# untitledV2.net
KiCad netlist of a schematic drawn in EAGLE
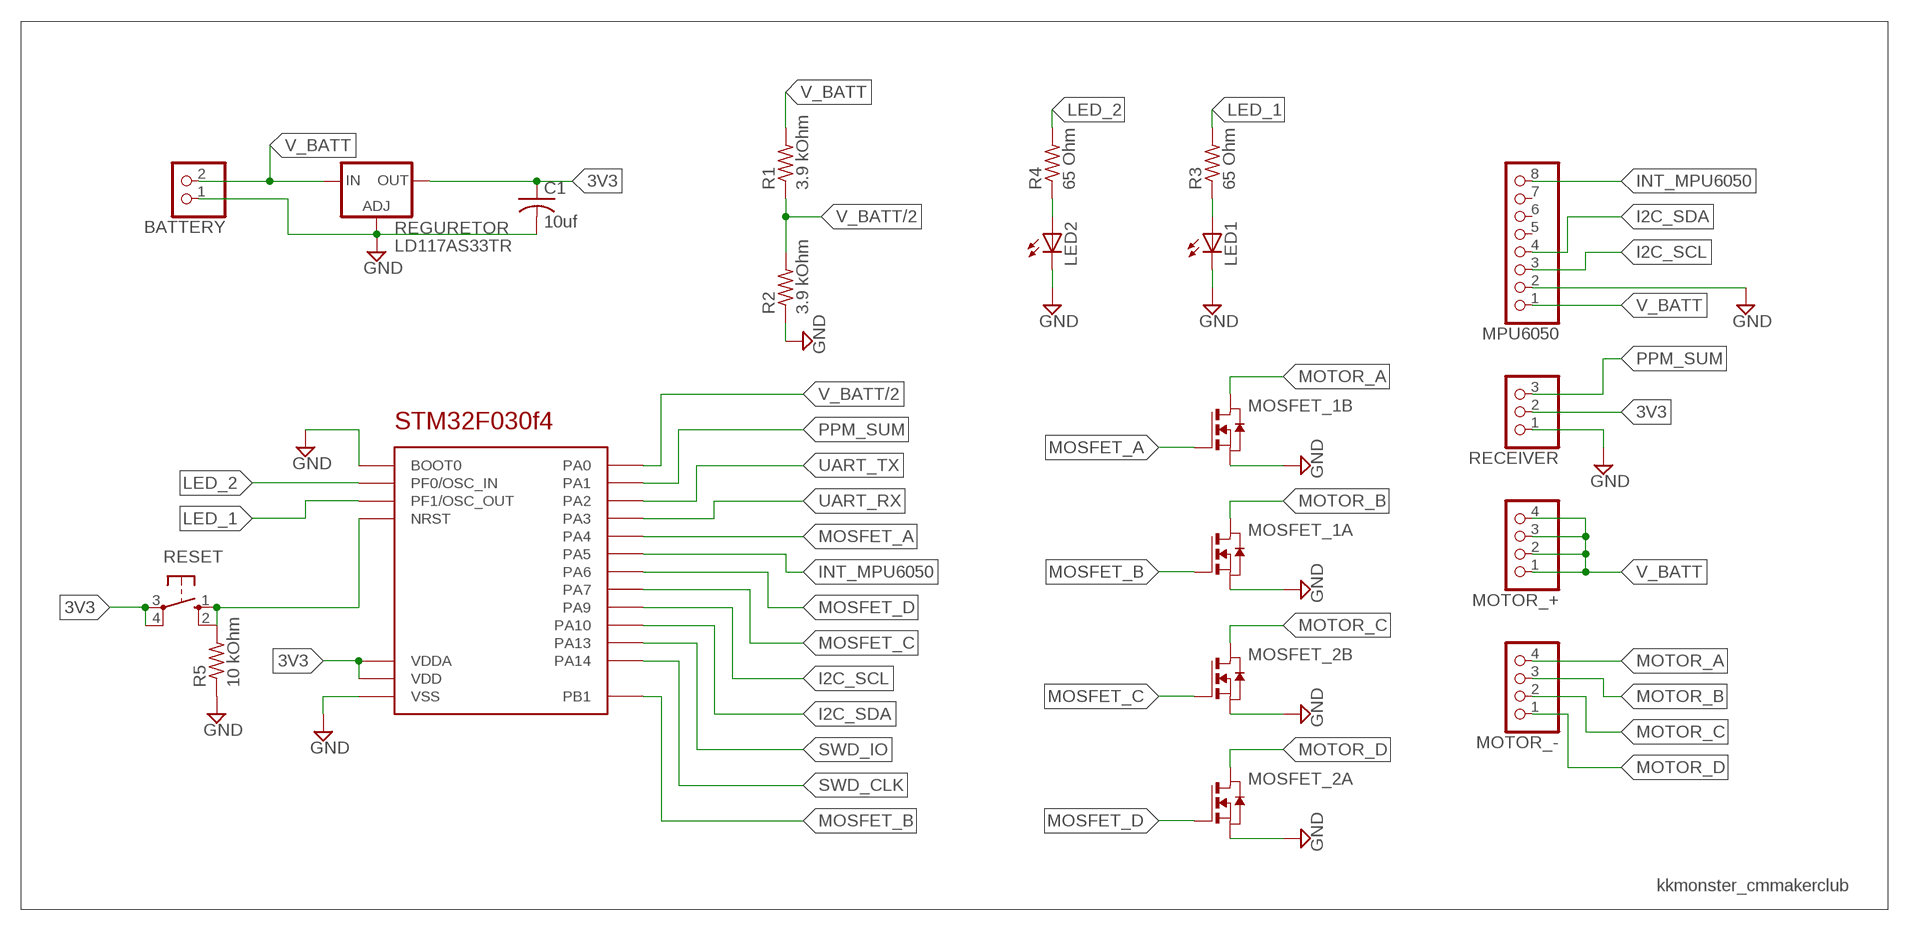
[diagram p0: schematic, sheet 1]

(export (version "E")
  (design (tool "Eeschema 10.0.6"))
  (components
    (comp (ref "BATTERY")
      (value "PINHD-1X2")
      (footprint "eagle-import:1X02")
      (libsource (lib "eagle-import") (part "PINHD-1X2"))
    )
    (comp (ref "C1")
      (value "10uf")
      (footprint "eagle-import:C1206")
      (libsource (lib "eagle-import") (part "C-USC1206"))
    )
    (comp (ref "LED1")
      (value "LEDSMT1206")
      (footprint "eagle-import:1206")
      (libsource (lib "eagle-import") (part "LEDSMT1206"))
    )
    (comp (ref "LED2")
      (value "LEDSMT1206")
      (footprint "eagle-import:1206")
      (libsource (lib "eagle-import") (part "LEDSMT1206"))
    )
    (comp (ref "MOSFET_1")
      (value "DMN3024LSD")
      (footprint "eagle-import:SO8")
      (libsource (lib "eagle-import") (part "DMN3024LSD"))
    )
    (comp (ref "MOSFET_2")
      (value "DMN3024LSD")
      (footprint "eagle-import:SO8")
      (libsource (lib "eagle-import") (part "DMN3024LSD"))
    )
    (comp (ref "MOTOR_+")
      (value "PINHD-1X4")
      (footprint "eagle-import:1X04")
      (libsource (lib "eagle-import") (part "PINHD-1X4"))
    )
    (comp (ref "MOTOR_-")
      (value "PINHD-1X4")
      (footprint "eagle-import:1X04")
      (libsource (lib "eagle-import") (part "PINHD-1X4"))
    )
    (comp (ref "MPU6050")
      (value "PINHD-1X8")
      (footprint "eagle-import:1X08")
      (libsource (lib "eagle-import") (part "PINHD-1X8"))
    )
    (comp (ref "R1")
      (value "3.9 kOhm")
      (footprint "eagle-import:R1206")
      (libsource (lib "eagle-import") (part "R-US_R1206"))
    )
    (comp (ref "R2")
      (value "3.9 kOhm")
      (footprint "eagle-import:R1206")
      (libsource (lib "eagle-import") (part "R-US_R1206"))
    )
    (comp (ref "R3")
      (value "65 Ohm")
      (footprint "eagle-import:R1206")
      (libsource (lib "eagle-import") (part "R-US_R1206"))
    )
    (comp (ref "R4")
      (value "65 Ohm")
      (footprint "eagle-import:R1206")
      (libsource (lib "eagle-import") (part "R-US_R1206"))
    )
    (comp (ref "R5")
      (value "10 kOhm")
      (footprint "eagle-import:R1206")
      (libsource (lib "eagle-import") (part "R-US_R1206"))
    )
    (comp (ref "RECEIVER")
      (value "PINHD-1X3")
      (footprint "eagle-import:1X03")
      (libsource (lib "eagle-import") (part "PINHD-1X3"))
    )
    (comp (ref "REGURETOR")
      (value "LD117AS33TR")
      (footprint "eagle-import:SOT223")
      (libsource (lib "eagle-import") (part "LD117A?S33TR"))
    )
    (comp (ref "RESET")
      (value "10-XX")
      (footprint "eagle-import:B3F-10XX")
      (fields (field (name "MPN") "B3F-1000"))
      (libsource (lib "eagle-import") (part "10-XX"))
    )
    (comp (ref "U$1")
      (value "STM32F030X4")
      (footprint "eagle-import:TSSOP20")
      (libsource (lib "eagle-import") (part "STM32F030X4"))
    )
  )
  (nets
    (net (code "1") (name "3V3") (class "Default")
      (node (ref "C1") (pin "1") (pinfunction "1_1") (pintype "passive"))
      (node (ref "RECEIVER") (pin "2") (pinfunction "2_2") (pintype "passive"))
      (node (ref "REGURETOR") (pin "4") (pinfunction "OUT_4") (pintype "passive"))
      (node (ref "RESET") (pin "3") (pinfunction "P_3") (pintype "passive"))
      (node (ref "RESET") (pin "4") (pinfunction "P1_4") (pintype "passive"))
      (node (ref "U$1") (pin "P$16") (pinfunction "VDD_P$16") (pintype "power_in"))
      (node (ref "U$1") (pin "P$5") (pinfunction "VDDA_P$5") (pintype "power_in"))
    )
    (net (code "2") (name "GND") (class "Default")
      (node (ref "BATTERY") (pin "1") (pinfunction "1_1") (pintype "passive"))
      (node (ref "C1") (pin "2") (pinfunction "2_2") (pintype "passive"))
      (node (ref "LED1") (pin "C") (pinfunction "C_C") (pintype "passive"))
      (node (ref "LED2") (pin "C") (pinfunction "C_C") (pintype "passive"))
      (node (ref "MOSFET_1") (pin "1") (pinfunction "S_1") (pintype "passive"))
      (node (ref "MOSFET_1") (pin "3") (pinfunction "S_3") (pintype "passive"))
      (node (ref "MOSFET_2") (pin "1") (pinfunction "S_1") (pintype "passive"))
      (node (ref "MOSFET_2") (pin "3") (pinfunction "S_3") (pintype "passive"))
      (node (ref "MPU6050") (pin "2") (pinfunction "2_2") (pintype "passive"))
      (node (ref "R2") (pin "1") (pinfunction "1_1") (pintype "passive"))
      (node (ref "R5") (pin "1") (pinfunction "1_1") (pintype "passive"))
      (node (ref "RECEIVER") (pin "1") (pinfunction "1_1") (pintype "passive"))
      (node (ref "REGURETOR") (pin "1") (pinfunction "ADJ_1") (pintype "input"))
      (node (ref "U$1") (pin "P$1") (pinfunction "BOOT0_P$1") (pintype "power_in"))
      (node (ref "U$1") (pin "P$15") (pinfunction "VSS_P$15") (pintype "power_in"))
    )
    (net (code "3") (name "I2C_SCL") (class "Default")
      (node (ref "MPU6050") (pin "3") (pinfunction "3_3") (pintype "passive"))
      (node (ref "U$1") (pin "P$17") (pinfunction "PA9_P$17") (pintype "bidirectional"))
    )
    (net (code "4") (name "I2C_SDA") (class "Default")
      (node (ref "MPU6050") (pin "4") (pinfunction "4_4") (pintype "passive"))
      (node (ref "U$1") (pin "P$18") (pinfunction "PA10_P$18") (pintype "bidirectional"))
    )
    (net (code "5") (name "INT_MPU6050") (class "Default")
      (node (ref "MPU6050") (pin "8") (pinfunction "8_8") (pintype "passive"))
      (node (ref "U$1") (pin "P$11") (pinfunction "PA5_P$11") (pintype "bidirectional"))
    )
    (net (code "6") (name "LED_1") (class "Default")
      (node (ref "R3") (pin "2") (pinfunction "2_2") (pintype "passive"))
      (node (ref "U$1") (pin "P$3") (pinfunction "PF1/OSC_OUT_P$3") (pintype "open_collector"))
    )
    (net (code "7") (name "LED_2") (class "Default")
      (node (ref "R4") (pin "2") (pinfunction "2_2") (pintype "passive"))
      (node (ref "U$1") (pin "P$2") (pinfunction "PF0/OSC_IN_P$2") (pintype "open_collector"))
    )
    (net (code "8") (name "MOSFET_A") (class "Default")
      (node (ref "MOSFET_1") (pin "4") (pinfunction "G_4") (pintype "passive"))
      (node (ref "U$1") (pin "P$10") (pinfunction "PA4_P$10") (pintype "bidirectional"))
    )
    (net (code "9") (name "MOSFET_B") (class "Default")
      (node (ref "MOSFET_1") (pin "2") (pinfunction "G_2") (pintype "passive"))
      (node (ref "U$1") (pin "P$14") (pinfunction "PB1_P$14") (pintype "bidirectional"))
    )
    (net (code "10") (name "MOSFET_C") (class "Default")
      (node (ref "MOSFET_2") (pin "4") (pinfunction "G_4") (pintype "passive"))
      (node (ref "U$1") (pin "P$13") (pinfunction "PA7_P$13") (pintype "bidirectional"))
    )
    (net (code "11") (name "MOSFET_D") (class "Default")
      (node (ref "MOSFET_2") (pin "2") (pinfunction "G_2") (pintype "passive"))
      (node (ref "U$1") (pin "P$12") (pinfunction "PA6_P$12") (pintype "bidirectional"))
    )
    (net (code "12") (name "MOTOR_A") (class "Default")
      (node (ref "MOSFET_1") (pin "5") (pinfunction "D_5") (pintype "passive"))
      (node (ref "MOSFET_1") (pin "6") (pinfunction "D_6") (pintype "passive"))
      (node (ref "MOTOR_-") (pin "4") (pinfunction "4_4") (pintype "passive"))
    )
    (net (code "13") (name "MOTOR_B") (class "Default")
      (node (ref "MOSFET_1") (pin "7") (pinfunction "D_7") (pintype "passive"))
      (node (ref "MOSFET_1") (pin "8") (pinfunction "D_8") (pintype "passive"))
      (node (ref "MOTOR_-") (pin "3") (pinfunction "3_3") (pintype "passive"))
    )
    (net (code "14") (name "MOTOR_C") (class "Default")
      (node (ref "MOSFET_2") (pin "5") (pinfunction "D_5") (pintype "passive"))
      (node (ref "MOSFET_2") (pin "6") (pinfunction "D_6") (pintype "passive"))
      (node (ref "MOTOR_-") (pin "2") (pinfunction "2_2") (pintype "passive"))
    )
    (net (code "15") (name "MOTOR_D") (class "Default")
      (node (ref "MOSFET_2") (pin "7") (pinfunction "D_7") (pintype "passive"))
      (node (ref "MOSFET_2") (pin "8") (pinfunction "D_8") (pintype "passive"))
      (node (ref "MOTOR_-") (pin "1") (pinfunction "1_1") (pintype "passive"))
    )
    (net (code "16") (name "Net-(LED1-PadA)") (class "Default")
      (node (ref "LED1") (pin "A") (pinfunction "A_A") (pintype "passive"))
      (node (ref "R3") (pin "1") (pinfunction "1_1") (pintype "passive"))
    )
    (net (code "17") (name "Net-(LED2-PadA)") (class "Default")
      (node (ref "LED2") (pin "A") (pinfunction "A_A") (pintype "passive"))
      (node (ref "R4") (pin "1") (pinfunction "1_1") (pintype "passive"))
    )
    (net (code "18") (name "Net-(RESET-S)") (class "Default")
      (node (ref "R5") (pin "2") (pinfunction "2_2") (pintype "passive"))
      (node (ref "RESET") (pin "1") (pinfunction "S_1") (pintype "passive"))
      (node (ref "RESET") (pin "2") (pinfunction "S1_2") (pintype "passive"))
      (node (ref "U$1") (pin "P$4") (pinfunction "NRST_P$4") (pintype "bidirectional"))
    )
    (net (code "19") (name "PPM_SUM") (class "Default")
      (node (ref "RECEIVER") (pin "3") (pinfunction "3_3") (pintype "passive"))
      (node (ref "U$1") (pin "P$7") (pinfunction "PA1_P$7") (pintype "bidirectional"))
    )
    (net (code "20") (name "SWD_CLK") (class "Default")
      (node (ref "U$1") (pin "P$20") (pinfunction "PA14_P$20") (pintype "bidirectional"))
    )
    (net (code "21") (name "SWD_IO") (class "Default")
      (node (ref "U$1") (pin "P$19") (pinfunction "PA13_P$19") (pintype "bidirectional"))
    )
    (net (code "22") (name "UART_RX") (class "Default")
      (node (ref "U$1") (pin "P$9") (pinfunction "PA3_P$9") (pintype "bidirectional"))
    )
    (net (code "23") (name "UART_TX") (class "Default")
      (node (ref "U$1") (pin "P$8") (pinfunction "PA2_P$8") (pintype "bidirectional"))
    )
    (net (code "24") (name "V_BATT") (class "Default")
      (node (ref "BATTERY") (pin "2") (pinfunction "2_2") (pintype "passive"))
      (node (ref "MOTOR_+") (pin "1") (pinfunction "1_1") (pintype "passive"))
      (node (ref "MOTOR_+") (pin "2") (pinfunction "2_2") (pintype "passive"))
      (node (ref "MOTOR_+") (pin "3") (pinfunction "3_3") (pintype "passive"))
      (node (ref "MOTOR_+") (pin "4") (pinfunction "4_4") (pintype "passive"))
      (node (ref "MPU6050") (pin "1") (pinfunction "1_1") (pintype "passive"))
      (node (ref "R1") (pin "2") (pinfunction "2_2") (pintype "passive"))
      (node (ref "REGURETOR") (pin "3") (pinfunction "IN_3") (pintype "input"))
    )
    (net (code "25") (name "V_BATT{slash}2") (class "Default")
      (node (ref "R1") (pin "1") (pinfunction "1_1") (pintype "passive"))
      (node (ref "R2") (pin "2") (pinfunction "2_2") (pintype "passive"))
      (node (ref "U$1") (pin "P$6") (pinfunction "PA0_P$6") (pintype "bidirectional"))
    )
    (net (code "26") (name "unconnected-(MPU6050-Pad5)") (class "Default")
      (node (ref "MPU6050") (pin "5") (pinfunction "5_5") (pintype "passive"))
    )
    (net (code "27") (name "unconnected-(MPU6050-Pad6)") (class "Default")
      (node (ref "MPU6050") (pin "6") (pinfunction "6_6") (pintype "passive"))
    )
    (net (code "28") (name "unconnected-(MPU6050-Pad7)") (class "Default")
      (node (ref "MPU6050") (pin "7") (pinfunction "7_7") (pintype "passive"))
    )
  )
)
